# board_supply_440v.net
KiCad netlist of a schematic drawn in Altium Designer
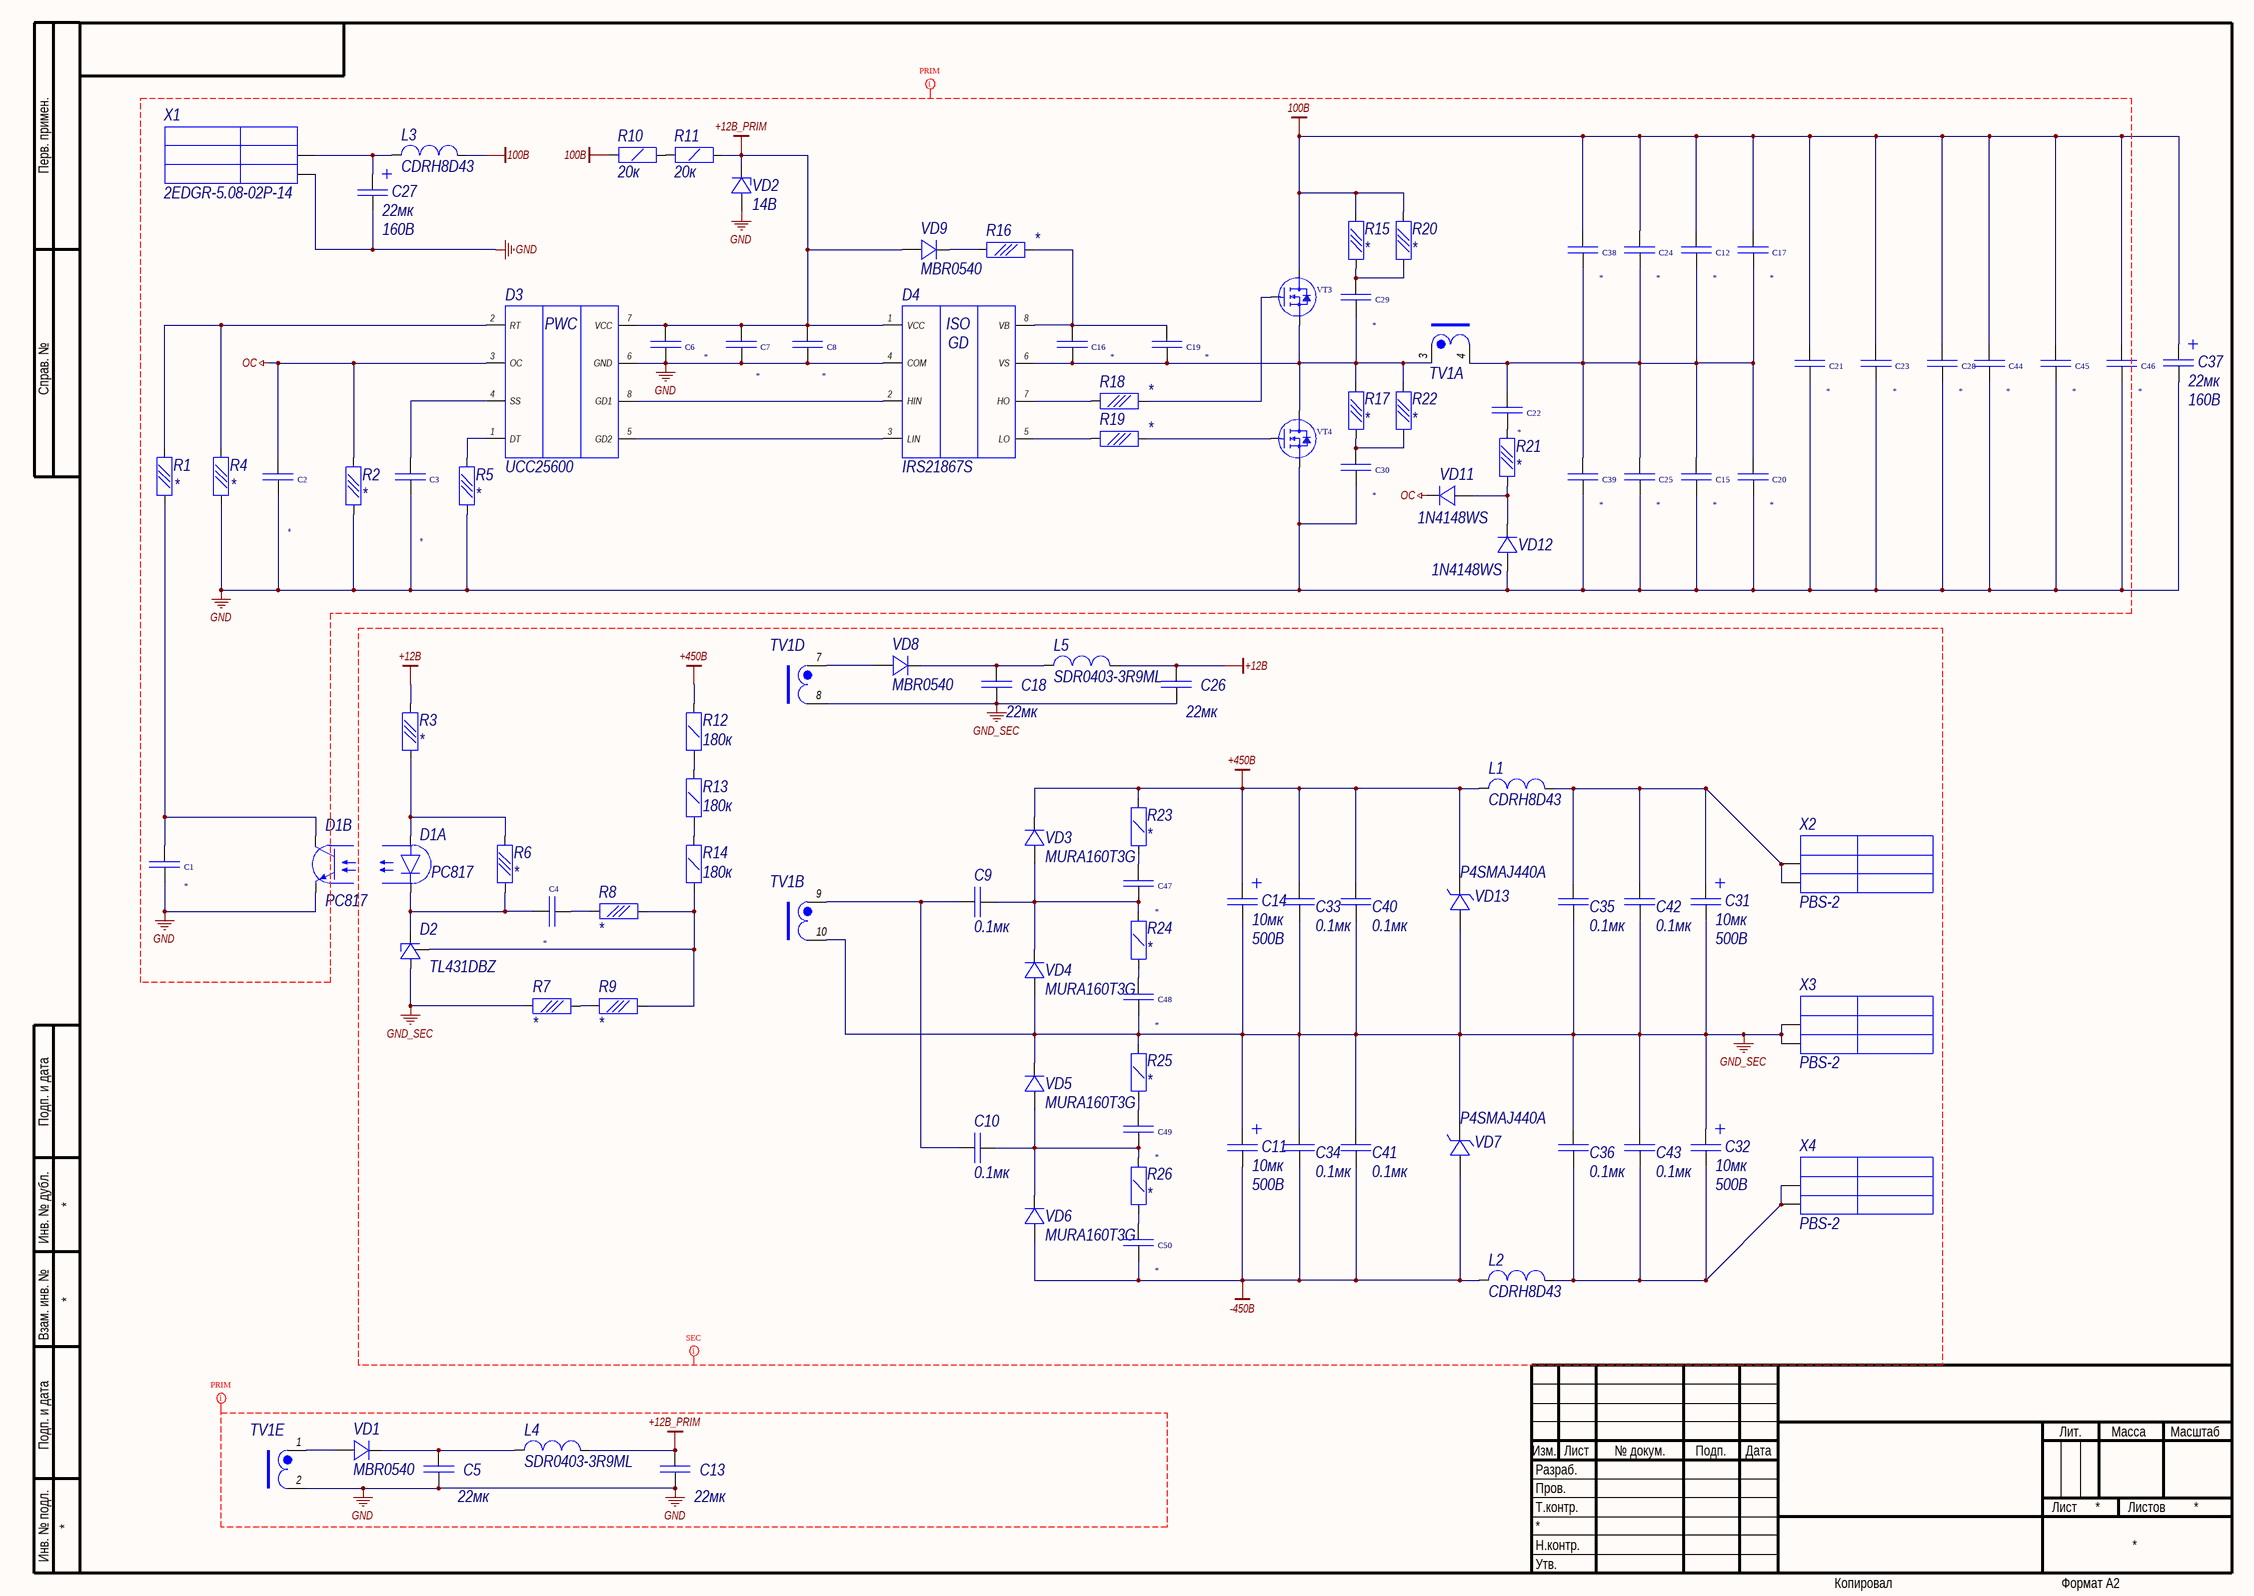
[diagram p0: board_supply_440v.SchDoc]

(export (version "E")
  (design (tool "Eeschema 10.0.6"))
  (components
    (comp (ref "C1") (value "*") (footprint "C-0603") (libsource (lib "Capacitor") (part "C0603")))
    (comp (ref "C2") (value "*") (footprint "C-0603") (libsource (lib "Capacitor") (part "C0603")))
    (comp (ref "C3") (value "*") (footprint "C-0603") (libsource (lib "Capacitor") (part "C0603")))
    (comp (ref "C4") (value "*") (footprint "C-0603") (libsource (lib "Capacitor") (part "C0603")))
    (comp (ref "C5")
      (value "22мк")
      (footprint "C-1206")
      (fields (field (name "VOLTAGE") "25"))
      (libsource (lib "Capacitor") (part "C1206"))
    )
    (comp (ref "C6") (value "*") (footprint "C-0603") (libsource (lib "Capacitor") (part "C0603")))
    (comp (ref "C7") (value "*") (footprint "C-0603") (libsource (lib "Capacitor") (part "C0603")))
    (comp (ref "C8") (value "*") (footprint "C-0603") (libsource (lib "Capacitor") (part "C0603")))
    (comp (ref "C9")
      (value "0.1мк")
      (footprint "C-1812")
      (fields (field (name "VOLTAGE") "630"))
      (libsource (lib "Capacitor") (part "C1812"))
    )
    (comp (ref "C10")
      (value "0.1мк")
      (footprint "C-1812")
      (fields (field (name "VOLTAGE") "630"))
      (libsource (lib "Capacitor") (part "C1812"))
    )
    (comp (ref "C11")
      (value "10мк")
      (footprint "CAP: D13C5H25")
      (description "Конденсатор электролитический")
      (fields (field (name "VOLTAGE") "500В"))
      (libsource (lib "Capacitor") (part "Aluminum electrolytic capacitor"))
    )
    (comp (ref "C12") (value "*") (footprint "C-0603") (libsource (lib "Capacitor") (part "C0603")))
    (comp (ref "C13")
      (value "22мк")
      (footprint "C-1206")
      (fields (field (name "VOLTAGE") "25"))
      (libsource (lib "Capacitor") (part "C1206"))
    )
    (comp (ref "C14")
      (value "10мк")
      (footprint "CAP: D13C5H25")
      (description "Конденсатор электролитический")
      (fields (field (name "VOLTAGE") "500В"))
      (libsource (lib "Capacitor") (part "Aluminum electrolytic capacitor"))
    )
    (comp (ref "C15") (value "*") (footprint "C-0603") (libsource (lib "Capacitor") (part "C0603")))
    (comp (ref "C16") (value "*") (footprint "C-0603") (libsource (lib "Capacitor") (part "C0603")))
    (comp (ref "C17") (value "*") (footprint "C-0603") (libsource (lib "Capacitor") (part "C0603")))
    (comp (ref "C18")
      (value "22мк")
      (footprint "C-1206")
      (fields (field (name "VOLTAGE") "25"))
      (libsource (lib "Capacitor") (part "C1206"))
    )
    (comp (ref "C19") (value "*") (footprint "C-0603") (libsource (lib "Capacitor") (part "C0603")))
    (comp (ref "C20") (value "*") (footprint "C-0603") (libsource (lib "Capacitor") (part "C0603")))
    (comp (ref "C21") (value "*") (footprint "C-0603") (libsource (lib "Capacitor") (part "C0603")))
    (comp (ref "C22") (value "*") (footprint "C-0603") (libsource (lib "Capacitor") (part "C0603")))
    (comp (ref "C23") (value "*") (footprint "C-0603") (libsource (lib "Capacitor") (part "C0603")))
    (comp (ref "C24") (value "*") (footprint "C-0603") (libsource (lib "Capacitor") (part "C0603")))
    (comp (ref "C25") (value "*") (footprint "C-0603") (libsource (lib "Capacitor") (part "C0603")))
    (comp (ref "C26")
      (value "22мк")
      (footprint "C-1206")
      (fields (field (name "VOLTAGE") "25"))
      (libsource (lib "Capacitor") (part "C1206"))
    )
    (comp (ref "C27")
      (value "22мк")
      (footprint "CAP: D10C5H16")
      (description "Конденсатор электролитический")
      (fields (field (name "VOLTAGE") "160В"))
      (libsource (lib "Capacitor") (part "Aluminum electrolytic capacitor"))
    )
    (comp (ref "C28") (value "*") (footprint "C-0603") (libsource (lib "Capacitor") (part "C0603")))
    (comp (ref "C29") (value "*") (footprint "C-0603") (libsource (lib "Capacitor") (part "C0603")))
    (comp (ref "C30") (value "*") (footprint "C-0603") (libsource (lib "Capacitor") (part "C0603")))
    (comp (ref "C31")
      (value "10мк")
      (footprint "CAP: D13C5H25")
      (description "Конденсатор электролитический")
      (fields (field (name "VOLTAGE") "500В"))
      (libsource (lib "Capacitor") (part "Aluminum electrolytic capacitor"))
    )
    (comp (ref "C32")
      (value "10мк")
      (footprint "CAP: D13C5H25")
      (description "Конденсатор электролитический")
      (fields (field (name "VOLTAGE") "500В"))
      (libsource (lib "Capacitor") (part "Aluminum electrolytic capacitor"))
    )
    (comp (ref "C33")
      (value "0.1мк")
      (footprint "C-1812")
      (fields (field (name "VOLTAGE") "630"))
      (libsource (lib "Capacitor") (part "C1812"))
    )
    (comp (ref "C34")
      (value "0.1мк")
      (footprint "C-1812")
      (fields (field (name "VOLTAGE") "630"))
      (libsource (lib "Capacitor") (part "C1812"))
    )
    (comp (ref "C35")
      (value "0.1мк")
      (footprint "C-1812")
      (fields (field (name "VOLTAGE") "630"))
      (libsource (lib "Capacitor") (part "C1812"))
    )
    (comp (ref "C36")
      (value "0.1мк")
      (footprint "C-1812")
      (fields (field (name "VOLTAGE") "630"))
      (libsource (lib "Capacitor") (part "C1812"))
    )
    (comp (ref "C37")
      (value "22мк")
      (footprint "CAP: D10C5H16")
      (description "Конденсатор электролитический")
      (fields (field (name "VOLTAGE") "160В"))
      (libsource (lib "Capacitor") (part "Aluminum electrolytic capacitor"))
    )
    (comp (ref "C38") (value "*") (footprint "C-0603") (libsource (lib "Capacitor") (part "C0603")))
    (comp (ref "C39") (value "*") (footprint "C-0603") (libsource (lib "Capacitor") (part "C0603")))
    (comp (ref "C40")
      (value "0.1мк")
      (footprint "C-1812")
      (fields (field (name "VOLTAGE") "630"))
      (libsource (lib "Capacitor") (part "C1812"))
    )
    (comp (ref "C41")
      (value "0.1мк")
      (footprint "C-1812")
      (fields (field (name "VOLTAGE") "630"))
      (libsource (lib "Capacitor") (part "C1812"))
    )
    (comp (ref "C42")
      (value "0.1мк")
      (footprint "C-1812")
      (fields (field (name "VOLTAGE") "630"))
      (libsource (lib "Capacitor") (part "C1812"))
    )
    (comp (ref "C43")
      (value "0.1мк")
      (footprint "C-1812")
      (fields (field (name "VOLTAGE") "630"))
      (libsource (lib "Capacitor") (part "C1812"))
    )
    (comp (ref "C44") (value "*") (footprint "C-0603") (libsource (lib "Capacitor") (part "C0603")))
    (comp (ref "C45") (value "*") (footprint "C-0603") (libsource (lib "Capacitor") (part "C0603")))
    (comp (ref "C46") (value "*") (footprint "C-0603") (libsource (lib "Capacitor") (part "C0603")))
    (comp (ref "C47") (value "*") (footprint "C-1206") (libsource (lib "Capacitor") (part "C1206")))
    (comp (ref "C48") (value "*") (footprint "C-1206") (libsource (lib "Capacitor") (part "C1206")))
    (comp (ref "C49") (value "*") (footprint "C-1206") (libsource (lib "Capacitor") (part "C1206")))
    (comp (ref "C50") (value "*") (footprint "C-1206") (libsource (lib "Capacitor") (part "C1206")))
    (comp (ref "D1")
      (value "PC817")
      (footprint "DIP4-SMD")
      (description "Оптрон с транзисторным выходом")
      (libsource (lib "OPTO") (part "PC817"))
    )
    (comp (ref "D2")
      (value "TL431DBZ")
      (footprint "SOT-23-3")
      (description "Микросхема ИОН")
      (libsource (lib "IC_Linear_Regulator") (part "TL431DBZ"))
    )
    (comp (ref "D3")
      (value "UCC25600")
      (footprint "8-SOIC")
      (description "Микросхема контроллер LLC")
      (libsource (lib "Power Controllers") (part "UCC25600"))
    )
    (comp (ref "D4")
      (value "IRS21867S")
      (footprint "8-SOIC")
      (description "Микросхема полумостовой драйвер")
      (libsource (lib "Power Controllers") (part "IRS21867S"))
    )
    (comp (ref "L1")
      (value "CDRH8D43")
      (footprint "L-8.3x8.3x4.5")
      (description "SMD дроссель")
      (libsource (lib "INDUCTORS") (part "CDRH8D43"))
    )
    (comp (ref "L2")
      (value "CDRH8D43")
      (footprint "L-8.3x8.3x4.5")
      (description "SMD дроссель")
      (libsource (lib "INDUCTORS") (part "CDRH8D43"))
    )
    (comp (ref "L3")
      (value "CDRH8D43")
      (footprint "L-8.3x8.3x4.5")
      (description "SMD дроссель")
      (libsource (lib "INDUCTORS") (part "CDRH8D43"))
    )
    (comp (ref "L4")
      (value "SDR0403-3R9ML")
      (footprint "L-4.5x4x3.2")
      (libsource (lib "INDUCTORS") (part "SDR0403-3R9ML"))
    )
    (comp (ref "L5")
      (value "SDR0403-3R9ML")
      (footprint "L-4.5x4x3.2")
      (libsource (lib "INDUCTORS") (part "SDR0403-3R9ML"))
    )
    (comp (ref "R1")
      (value "*")
      (footprint "R-0603")
      (description "Резистор SMD")
      (fields (field (name "TOLERANCE") "5%"))
      (libsource (lib "Resistor") (part "R0603"))
    )
    (comp (ref "R2")
      (value "*")
      (footprint "R-0603")
      (description "Резистор SMD")
      (fields (field (name "TOLERANCE") "5%"))
      (libsource (lib "Resistor") (part "R0603"))
    )
    (comp (ref "R3")
      (value "*")
      (footprint "R-0603")
      (description "Резистор SMD")
      (fields (field (name "TOLERANCE") "5%"))
      (libsource (lib "Resistor") (part "R0603"))
    )
    (comp (ref "R4")
      (value "*")
      (footprint "R-0603")
      (description "Резистор SMD")
      (fields (field (name "TOLERANCE") "5%"))
      (libsource (lib "Resistor") (part "R0603"))
    )
    (comp (ref "R5")
      (value "*")
      (footprint "R-0603")
      (description "Резистор SMD")
      (fields (field (name "TOLERANCE") "5%"))
      (libsource (lib "Resistor") (part "R0603"))
    )
    (comp (ref "R6")
      (value "*")
      (footprint "R-0603")
      (description "Резистор SMD")
      (fields (field (name "TOLERANCE") "5%"))
      (libsource (lib "Resistor") (part "R0603"))
    )
    (comp (ref "R7")
      (value "*")
      (footprint "R-0603")
      (description "Резистор SMD")
      (fields (field (name "TOLERANCE") "5%"))
      (libsource (lib "Resistor") (part "R0603"))
    )
    (comp (ref "R8")
      (value "*")
      (footprint "R-0603")
      (description "Резистор SMD")
      (fields (field (name "TOLERANCE") "5%"))
      (libsource (lib "Resistor") (part "R0603"))
    )
    (comp (ref "R9")
      (value "*")
      (footprint "R-0603")
      (description "Резистор SMD")
      (fields (field (name "TOLERANCE") "5%"))
      (libsource (lib "Resistor") (part "R0603"))
    )
    (comp (ref "R10")
      (value "20к")
      (footprint "R-1206")
      (description "Резистор SMD")
      (fields (field (name "TOLERANCE") "5%"))
      (libsource (lib "Resistor") (part "R1206"))
    )
    (comp (ref "R11")
      (value "20к")
      (footprint "R-1206")
      (description "Резистор SMD")
      (fields (field (name "TOLERANCE") "5%"))
      (libsource (lib "Resistor") (part "R1206"))
    )
    (comp (ref "R12")
      (value "180к")
      (footprint "R-1206")
      (description "Резистор SMD")
      (fields (field (name "TOLERANCE") "5%"))
      (libsource (lib "Resistor") (part "R1206"))
    )
    (comp (ref "R13")
      (value "180к")
      (footprint "R-1206")
      (description "Резистор SMD")
      (fields (field (name "TOLERANCE") "5%"))
      (libsource (lib "Resistor") (part "R1206"))
    )
    (comp (ref "R14")
      (value "180к")
      (footprint "R-1206")
      (description "Резистор SMD")
      (fields (field (name "TOLERANCE") "5%"))
      (libsource (lib "Resistor") (part "R1206"))
    )
    (comp (ref "R15")
      (value "*")
      (footprint "R-0603")
      (description "Резистор SMD")
      (fields (field (name "TOLERANCE") "5%"))
      (libsource (lib "Resistor") (part "R0603"))
    )
    (comp (ref "R16")
      (value "*")
      (footprint "R-0603")
      (description "Резистор SMD")
      (fields (field (name "TOLERANCE") "5%"))
      (libsource (lib "Resistor") (part "R0603"))
    )
    (comp (ref "R17")
      (value "*")
      (footprint "R-0603")
      (description "Резистор SMD")
      (fields (field (name "TOLERANCE") "5%"))
      (libsource (lib "Resistor") (part "R0603"))
    )
    (comp (ref "R18")
      (value "*")
      (footprint "R-0603")
      (description "Резистор SMD")
      (fields (field (name "TOLERANCE") "5%"))
      (libsource (lib "Resistor") (part "R0603"))
    )
    (comp (ref "R19")
      (value "*")
      (footprint "R-0603")
      (description "Резистор SMD")
      (fields (field (name "TOLERANCE") "5%"))
      (libsource (lib "Resistor") (part "R0603"))
    )
    (comp (ref "R20")
      (value "*")
      (footprint "R-0603")
      (description "Резистор SMD")
      (fields (field (name "TOLERANCE") "5%"))
      (libsource (lib "Resistor") (part "R0603"))
    )
    (comp (ref "R21")
      (value "*")
      (footprint "R-0603")
      (description "Резистор SMD")
      (fields (field (name "TOLERANCE") "5%"))
      (libsource (lib "Resistor") (part "R0603"))
    )
    (comp (ref "R22")
      (value "*")
      (footprint "R-0603")
      (description "Резистор SMD")
      (fields (field (name "TOLERANCE") "5%"))
      (libsource (lib "Resistor") (part "R0603"))
    )
    (comp (ref "R23")
      (value "*")
      (footprint "R-1206")
      (description "Резистор SMD")
      (fields (field (name "TOLERANCE") "5%"))
      (libsource (lib "Resistor") (part "R1206"))
    )
    (comp (ref "R24")
      (value "*")
      (footprint "R-1206")
      (description "Резистор SMD")
      (fields (field (name "TOLERANCE") "5%"))
      (libsource (lib "Resistor") (part "R1206"))
    )
    (comp (ref "R25")
      (value "*")
      (footprint "R-1206")
      (description "Резистор SMD")
      (fields (field (name "TOLERANCE") "5%"))
      (libsource (lib "Resistor") (part "R1206"))
    )
    (comp (ref "R26")
      (value "*")
      (footprint "R-1206")
      (description "Резистор SMD")
      (fields (field (name "TOLERANCE") "5%"))
      (libsource (lib "Resistor") (part "R1206"))
    )
    (comp (ref "TV1")
      (value "2xT26.9/14.7/11.2")
      (footprint "Transformers:EE30")
      (description "Трансформатор для board_supply_440v")
      (libsource (lib "Transformers") (part "2xT26.9/14.7/11.2"))
    )
    (comp (ref "VD1")
      (value "MBR0540")
      (footprint "SOD-123FL")
      (description "Диод выпрямительный одиночный")
      (libsource (lib "DIODES") (part "MBR0540"))
    )
    (comp (ref "VD2")
      (value "14В")
      (footprint "SOD-323")
      (description "Диод Зенера (стабилитрон)")
      (libsource (lib "DIODES") (part "MM3Z"))
    )
    (comp (ref "VD3")
      (value "MURA160T3G")
      (footprint "DO-214AC")
      (description "Диод выпрямительный одиночный")
      (libsource (lib "DIODES") (part "MURA160T3G"))
    )
    (comp (ref "VD4")
      (value "MURA160T3G")
      (footprint "DO-214AC")
      (description "Диод выпрямительный одиночный")
      (libsource (lib "DIODES") (part "MURA160T3G"))
    )
    (comp (ref "VD5")
      (value "MURA160T3G")
      (footprint "DO-214AC")
      (description "Диод выпрямительный одиночный")
      (libsource (lib "DIODES") (part "MURA160T3G"))
    )
    (comp (ref "VD6")
      (value "MURA160T3G")
      (footprint "DO-214AC")
      (description "Диод выпрямительный одиночный")
      (libsource (lib "DIODES") (part "MURA160T3G"))
    )
    (comp (ref "VD7")
      (value "P4SMAJ440A")
      (footprint "DO-214AC")
      (description "Защитный диод униполярный")
      (libsource (lib "DIODES") (part "P4SMAJ-XX-A"))
    )
    (comp (ref "VD8")
      (value "MBR0540")
      (footprint "SOD-123FL")
      (description "Диод выпрямительный одиночный")
      (libsource (lib "DIODES") (part "MBR0540"))
    )
    (comp (ref "VD9")
      (value "MBR0540")
      (footprint "SOD-123FL")
      (description "Диод выпрямительный одиночный")
      (libsource (lib "DIODES") (part "MBR0540"))
    )
    (comp (ref "VD11")
      (value "1N4148WS")
      (footprint "SOD-323")
      (description "Диод выпрямительный одиночный")
      (libsource (lib "DIODES") (part "1N4148WS"))
    )
    (comp (ref "VD12")
      (value "1N4148WS")
      (footprint "SOD-323")
      (description "Диод выпрямительный одиночный")
      (libsource (lib "DIODES") (part "1N4148WS"))
    )
    (comp (ref "VD13")
      (value "P4SMAJ440A")
      (footprint "DO-214AC")
      (description "Защитный диод униполярный")
      (libsource (lib "DIODES") (part "P4SMAJ-XX-A"))
    )
    (comp (ref "VT3")
      (value "__GENERIC-N")
      (footprint "WDFN-8")
      (description "Транзистор МОП, одиночный, N-канальный")
      (libsource (lib "MOSFET_POWER") (part "__GENERIC-N"))
    )
    (comp (ref "VT4")
      (value "__GENERIC-N")
      (footprint "WDFN-8")
      (description "Транзистор МОП, одиночный, N-канальный")
      (libsource (lib "MOSFET_POWER") (part "__GENERIC-N"))
    )
    (comp (ref "X1")
      (value "2EDGR-5.08-02P-14")
      (footprint "2EDGR-5.08-02P-14-00AH")
      (description "Разъем разрывной")
      (libsource (lib "CONNECTORS") (part "2EDGR-5.08-02P-14-00AH"))
    )
    (comp (ref "X2")
      (value "PBS-2")
      (footprint "PBS-2")
      (description "Разъём штыревой")
      (libsource (lib "CONNECTORS") (part "PBS-2"))
    )
    (comp (ref "X3")
      (value "PBS-2")
      (footprint "PBS-2")
      (description "Разъём штыревой")
      (libsource (lib "CONNECTORS") (part "PBS-2"))
    )
    (comp (ref "X4")
      (value "PBS-2")
      (footprint "PBS-2")
      (description "Разъём штыревой")
      (libsource (lib "CONNECTORS") (part "PBS-2"))
    )
  )
  (nets
    (net (code "1") (name "+12В") (class "Default")
      (node (ref "C26") (pin "1") (pintype "passive"))
      (node (ref "L5") (pin "1") (pinfunction "1_1") (pintype "passive"))
      (node (ref "R3") (pin "2") (pintype "passive"))
    )
    (net (code "2") (name "+12В_PRIM") (class "Default")
      (node (ref "C13") (pin "1") (pintype "passive"))
      (node (ref "C6") (pin "2") (pintype "passive"))
      (node (ref "C7") (pin "2") (pintype "passive"))
      (node (ref "C8") (pin "2") (pintype "passive"))
      (node (ref "D3") (pin "7") (pinfunction "VCC_7") (pintype "passive"))
      (node (ref "D4") (pin "1") (pinfunction "VCC_1") (pintype "passive"))
      (node (ref "L4") (pin "1") (pinfunction "1_1") (pintype "passive"))
      (node (ref "R11") (pin "1") (pintype "passive"))
      (node (ref "VD2") (pin "K") (pinfunction "K_K") (pintype "passive"))
      (node (ref "VD9") (pin "A") (pinfunction "A_A") (pintype "passive"))
    )
    (net (code "3") (name "+450В") (class "Default")
      (node (ref "C14") (pin "1") (pintype "passive"))
      (node (ref "C33") (pin "1") (pintype "passive"))
      (node (ref "C40") (pin "1") (pintype "passive"))
      (node (ref "L1") (pin "2") (pinfunction "2_2") (pintype "passive"))
      (node (ref "R12") (pin "2") (pintype "passive"))
      (node (ref "R23") (pin "1") (pintype "passive"))
      (node (ref "VD13") (pin "K") (pinfunction "K_K") (pintype "passive"))
      (node (ref "VD3") (pin "K") (pinfunction "K_K") (pintype "passive"))
    )
    (net (code "4") (name "-450В") (class "Default")
      (node (ref "C11") (pin "2") (pintype "passive"))
      (node (ref "C34") (pin "2") (pintype "passive"))
      (node (ref "C41") (pin "2") (pintype "passive"))
      (node (ref "C50") (pin "1") (pintype "passive"))
      (node (ref "L2") (pin "2") (pinfunction "2_2") (pintype "passive"))
      (node (ref "VD6") (pin "A") (pinfunction "A_A") (pintype "passive"))
      (node (ref "VD7") (pin "A") (pinfunction "A_A") (pintype "passive"))
    )
    (net (code "5") (name "100В") (class "Default")
      (node (ref "C12") (pin "2") (pintype "passive"))
      (node (ref "C17") (pin "2") (pintype "passive"))
      (node (ref "C21") (pin "2") (pintype "passive"))
      (node (ref "C23") (pin "2") (pintype "passive"))
      (node (ref "C24") (pin "2") (pintype "passive"))
      (node (ref "C28") (pin "2") (pintype "passive"))
      (node (ref "C37") (pin "1") (pintype "passive"))
      (node (ref "C38") (pin "2") (pintype "passive"))
      (node (ref "C44") (pin "2") (pintype "passive"))
      (node (ref "C45") (pin "2") (pintype "passive"))
      (node (ref "C46") (pin "2") (pintype "passive"))
      (node (ref "L3") (pin "1") (pinfunction "1_1") (pintype "passive"))
      (node (ref "R10") (pin "2") (pintype "passive"))
      (node (ref "R15") (pin "1") (pintype "passive"))
      (node (ref "R20") (pin "1") (pintype "passive"))
      (node (ref "VT3") (pin "D") (pinfunction "D_D") (pintype "passive"))
    )
    (net (code "6") (name "GND") (class "Default")
      (node (ref "C1") (pin "1") (pintype "passive"))
      (node (ref "C13") (pin "2") (pintype "passive"))
      (node (ref "C15") (pin "1") (pintype "passive"))
      (node (ref "C2") (pin "1") (pintype "passive"))
      (node (ref "C20") (pin "1") (pintype "passive"))
      (node (ref "C21") (pin "1") (pintype "passive"))
      (node (ref "C23") (pin "1") (pintype "passive"))
      (node (ref "C25") (pin "1") (pintype "passive"))
      (node (ref "C27") (pin "2") (pintype "passive"))
      (node (ref "C28") (pin "1") (pintype "passive"))
      (node (ref "C3") (pin "1") (pintype "passive"))
      (node (ref "C30") (pin "1") (pintype "passive"))
      (node (ref "C37") (pin "2") (pintype "passive"))
      (node (ref "C39") (pin "1") (pintype "passive"))
      (node (ref "C44") (pin "1") (pintype "passive"))
      (node (ref "C45") (pin "1") (pintype "passive"))
      (node (ref "C46") (pin "1") (pintype "passive"))
      (node (ref "C5") (pin "2") (pintype "passive"))
      (node (ref "C6") (pin "1") (pintype "passive"))
      (node (ref "C7") (pin "1") (pintype "passive"))
      (node (ref "C8") (pin "1") (pintype "passive"))
      (node (ref "D1") (pin "3") (pinfunction "E_3") (pintype "passive"))
      (node (ref "D3") (pin "6") (pinfunction "GND_6") (pintype "passive"))
      (node (ref "D4") (pin "4") (pinfunction "COM_4") (pintype "passive"))
      (node (ref "R2") (pin "1") (pintype "passive"))
      (node (ref "R4") (pin "1") (pintype "passive"))
      (node (ref "R5") (pin "1") (pintype "passive"))
      (node (ref "TV1") (pin "2") (pinfunction "2_2") (pintype "passive"))
      (node (ref "VD12") (pin "A") (pinfunction "A_A") (pintype "passive"))
      (node (ref "VD2") (pin "A") (pinfunction "A_A") (pintype "passive"))
      (node (ref "VT4") (pin "S") (pinfunction "S_S") (pintype "passive"))
      (node (ref "X1") (pin "2") (pintype "passive"))
    )
    (net (code "7") (name "GND_SEC") (class "Default")
      (node (ref "C11") (pin "1") (pintype "passive"))
      (node (ref "C14") (pin "2") (pintype "passive"))
      (node (ref "C18") (pin "2") (pintype "passive"))
      (node (ref "C26") (pin "2") (pintype "passive"))
      (node (ref "C31") (pin "2") (pintype "passive"))
      (node (ref "C32") (pin "1") (pintype "passive"))
      (node (ref "C33") (pin "2") (pintype "passive"))
      (node (ref "C34") (pin "1") (pintype "passive"))
      (node (ref "C35") (pin "2") (pintype "passive"))
      (node (ref "C36") (pin "1") (pintype "passive"))
      (node (ref "C40") (pin "2") (pintype "passive"))
      (node (ref "C41") (pin "1") (pintype "passive"))
      (node (ref "C42") (pin "2") (pintype "passive"))
      (node (ref "C43") (pin "1") (pintype "passive"))
      (node (ref "C48") (pin "1") (pintype "passive"))
      (node (ref "D2") (pin "3") (pinfunction "A_3") (pintype "passive"))
      (node (ref "R25") (pin "1") (pintype "passive"))
      (node (ref "R7") (pin "1") (pintype "passive"))
      (node (ref "TV1") (pin "10") (pinfunction "10_10") (pintype "passive"))
      (node (ref "TV1") (pin "8") (pinfunction "8_8") (pintype "passive"))
      (node (ref "VD13") (pin "A") (pinfunction "A_A") (pintype "passive"))
      (node (ref "VD4") (pin "A") (pinfunction "A_A") (pintype "passive"))
      (node (ref "VD5") (pin "K") (pinfunction "K_K") (pintype "passive"))
      (node (ref "VD7") (pin "K") (pinfunction "K_K") (pintype "passive"))
      (node (ref "X3") (pin "1") (pintype "passive"))
      (node (ref "X3") (pin "2") (pintype "passive"))
    )
    (net (code "8") (name "Net-(C4-Pad1)") (class "Default")
      (node (ref "C4") (pin "1") (pintype "passive"))
      (node (ref "R8") (pin "2") (pintype "passive"))
    )
    (net (code "9") (name "Net-(C5-Pad1)") (class "Default")
      (node (ref "C5") (pin "1") (pintype "passive"))
      (node (ref "L4") (pin "2") (pinfunction "2_2") (pintype "passive"))
      (node (ref "VD1") (pin "K") (pinfunction "K_K") (pintype "passive"))
    )
    (net (code "10") (name "Net-(C10-Pad1)") (class "Default")
      (node (ref "C10") (pin "1") (pintype "passive"))
      (node (ref "C49") (pin "1") (pintype "passive"))
      (node (ref "R26") (pin "1") (pintype "passive"))
      (node (ref "VD5") (pin "A") (pinfunction "A_A") (pintype "passive"))
      (node (ref "VD6") (pin "K") (pinfunction "K_K") (pintype "passive"))
    )
    (net (code "11") (name "Net-(C10-Pad2)") (class "Default")
      (node (ref "C10") (pin "2") (pintype "passive"))
      (node (ref "C9") (pin "2") (pintype "passive"))
      (node (ref "TV1") (pin "9") (pinfunction "9_9") (pintype "passive"))
    )
    (net (code "12") (name "Net-(C12-Pad1)") (class "Default")
      (node (ref "C12") (pin "1") (pintype "passive"))
      (node (ref "C15") (pin "2") (pintype "passive"))
      (node (ref "C17") (pin "1") (pintype "passive"))
      (node (ref "C20") (pin "2") (pintype "passive"))
      (node (ref "C22") (pin "1") (pintype "passive"))
      (node (ref "C24") (pin "1") (pintype "passive"))
      (node (ref "C25") (pin "2") (pintype "passive"))
      (node (ref "C38") (pin "1") (pintype "passive"))
      (node (ref "C39") (pin "2") (pintype "passive"))
      (node (ref "TV1") (pin "4") (pinfunction "4_4") (pintype "passive"))
    )
    (net (code "13") (name "Net-(C18-Pad1)") (class "Default")
      (node (ref "C18") (pin "1") (pintype "passive"))
      (node (ref "L5") (pin "2") (pinfunction "2_2") (pintype "passive"))
      (node (ref "VD8") (pin "K") (pinfunction "K_K") (pintype "passive"))
    )
    (net (code "14") (name "Net-(C22-Pad2)") (class "Default")
      (node (ref "C22") (pin "2") (pintype "passive"))
      (node (ref "R21") (pin "2") (pintype "passive"))
    )
    (net (code "15") (name "Net-(C27-Pad1)") (class "Default")
      (node (ref "C27") (pin "1") (pintype "passive"))
      (node (ref "L3") (pin "2") (pinfunction "2_2") (pintype "passive"))
      (node (ref "X1") (pin "1") (pintype "passive"))
    )
    (net (code "16") (name "Net-(C29-Pad2)") (class "Default")
      (node (ref "C29") (pin "2") (pintype "passive"))
      (node (ref "R15") (pin "2") (pintype "passive"))
      (node (ref "R20") (pin "2") (pintype "passive"))
    )
    (net (code "17") (name "Net-(C30-Pad2)") (class "Default")
      (node (ref "C30") (pin "2") (pintype "passive"))
      (node (ref "R17") (pin "2") (pintype "passive"))
      (node (ref "R22") (pin "2") (pintype "passive"))
    )
    (net (code "18") (name "Net-(C31-Pad1)") (class "Default")
      (node (ref "C31") (pin "1") (pintype "passive"))
      (node (ref "C35") (pin "1") (pintype "passive"))
      (node (ref "C42") (pin "1") (pintype "passive"))
      (node (ref "L1") (pin "1") (pinfunction "1_1") (pintype "passive"))
      (node (ref "X2") (pin "1") (pintype "passive"))
      (node (ref "X2") (pin "2") (pintype "passive"))
    )
    (net (code "19") (name "Net-(C32-Pad2)") (class "Default")
      (node (ref "C32") (pin "2") (pintype "passive"))
      (node (ref "C36") (pin "2") (pintype "passive"))
      (node (ref "C43") (pin "2") (pintype "passive"))
      (node (ref "L2") (pin "1") (pinfunction "1_1") (pintype "passive"))
      (node (ref "X4") (pin "1") (pintype "passive"))
      (node (ref "X4") (pin "2") (pintype "passive"))
    )
    (net (code "20") (name "Net-(C47-Pad1)") (class "Default")
      (node (ref "C47") (pin "1") (pintype "passive"))
      (node (ref "C9") (pin "1") (pintype "passive"))
      (node (ref "R24") (pin "1") (pintype "passive"))
      (node (ref "VD3") (pin "A") (pinfunction "A_A") (pintype "passive"))
      (node (ref "VD4") (pin "K") (pinfunction "K_K") (pintype "passive"))
    )
    (net (code "21") (name "Net-(C47-Pad2)") (class "Default")
      (node (ref "C47") (pin "2") (pintype "passive"))
      (node (ref "R23") (pin "2") (pintype "passive"))
    )
    (net (code "22") (name "Net-(C48-Pad2)") (class "Default")
      (node (ref "C48") (pin "2") (pintype "passive"))
      (node (ref "R24") (pin "2") (pintype "passive"))
    )
    (net (code "23") (name "Net-(C49-Pad2)") (class "Default")
      (node (ref "C49") (pin "2") (pintype "passive"))
      (node (ref "R25") (pin "2") (pintype "passive"))
    )
    (net (code "24") (name "Net-(C50-Pad2)") (class "Default")
      (node (ref "C50") (pin "2") (pintype "passive"))
      (node (ref "R26") (pin "2") (pintype "passive"))
    )
    (net (code "25") (name "Net-(D1A-A)") (class "Default")
      (node (ref "D1") (pin "1") (pinfunction "A_1") (pintype "passive"))
      (node (ref "R3") (pin "1") (pintype "passive"))
      (node (ref "R6") (pin "2") (pintype "passive"))
    )
    (net (code "26") (name "Net-(D1A-K)") (class "Default")
      (node (ref "C4") (pin "2") (pintype "passive"))
      (node (ref "D1") (pin "2") (pinfunction "K_2") (pintype "passive"))
      (node (ref "D2") (pin "1") (pinfunction "K_1") (pintype "passive"))
      (node (ref "R6") (pin "1") (pintype "passive"))
    )
    (net (code "27") (name "Net-(D1B-C)") (class "Default")
      (node (ref "C1") (pin "2") (pintype "passive"))
      (node (ref "D1") (pin "4") (pinfunction "C_4") (pintype "passive"))
      (node (ref "R1") (pin "1") (pintype "passive"))
    )
    (net (code "28") (name "Net-(D2-R)") (class "Default")
      (node (ref "D2") (pin "2") (pinfunction "R_2") (pintype "passive"))
      (node (ref "R14") (pin "1") (pintype "passive"))
      (node (ref "R8") (pin "1") (pintype "passive"))
      (node (ref "R9") (pin "2") (pintype "passive"))
    )
    (net (code "29") (name "Net-(D3-DT)") (class "Default")
      (node (ref "D3") (pin "1") (pinfunction "DT_1") (pintype "passive"))
      (node (ref "R5") (pin "2") (pintype "passive"))
    )
    (net (code "30") (name "Net-(D3-GD1)") (class "Default")
      (node (ref "D3") (pin "8") (pinfunction "GD1_8") (pintype "passive"))
      (node (ref "D4") (pin "2") (pinfunction "HIN_2") (pintype "passive"))
    )
    (net (code "31") (name "Net-(D3-GD2)") (class "Default")
      (node (ref "D3") (pin "5") (pinfunction "GD2_5") (pintype "passive"))
      (node (ref "D4") (pin "3") (pinfunction "LIN_3") (pintype "passive"))
    )
    (net (code "32") (name "Net-(D3-RT)") (class "Default")
      (node (ref "D3") (pin "2") (pinfunction "RT_2") (pintype "passive"))
      (node (ref "R1") (pin "2") (pintype "passive"))
      (node (ref "R4") (pin "2") (pintype "passive"))
    )
    (net (code "33") (name "Net-(D3-SS)") (class "Default")
      (node (ref "C3") (pin "2") (pintype "passive"))
      (node (ref "D3") (pin "4") (pinfunction "SS_4") (pintype "passive"))
    )
    (net (code "34") (name "Net-(D4-HO)") (class "Default")
      (node (ref "D4") (pin "7") (pinfunction "HO_7") (pintype "passive"))
      (node (ref "R18") (pin "1") (pintype "passive"))
    )
    (net (code "35") (name "Net-(D4-LO)") (class "Default")
      (node (ref "D4") (pin "5") (pinfunction "LO_5") (pintype "passive"))
      (node (ref "R19") (pin "1") (pintype "passive"))
    )
    (net (code "36") (name "Net-(D4-VB)") (class "Default")
      (node (ref "C16") (pin "2") (pintype "passive"))
      (node (ref "C19") (pin "2") (pintype "passive"))
      (node (ref "D4") (pin "8") (pinfunction "VB_8") (pintype "passive"))
      (node (ref "R16") (pin "2") (pintype "passive"))
    )
    (net (code "37") (name "Net-(D4-VS)") (class "Default")
      (node (ref "C16") (pin "1") (pintype "passive"))
      (node (ref "C19") (pin "1") (pintype "passive"))
      (node (ref "C29") (pin "1") (pintype "passive"))
      (node (ref "D4") (pin "6") (pinfunction "VS_6") (pintype "passive"))
      (node (ref "R17") (pin "1") (pintype "passive"))
      (node (ref "R22") (pin "1") (pintype "passive"))
      (node (ref "TV1") (pin "3") (pinfunction "3_3") (pintype "passive"))
      (node (ref "VT3") (pin "S") (pinfunction "S_S") (pintype "passive"))
      (node (ref "VT4") (pin "D") (pinfunction "D_D") (pintype "passive"))
    )
    (net (code "38") (name "Net-(R7-Pad2)") (class "Default")
      (node (ref "R7") (pin "2") (pintype "passive"))
      (node (ref "R9") (pin "1") (pintype "passive"))
    )
    (net (code "39") (name "Net-(R10-Pad1)") (class "Default")
      (node (ref "R10") (pin "1") (pintype "passive"))
      (node (ref "R11") (pin "2") (pintype "passive"))
    )
    (net (code "40") (name "Net-(R12-Pad1)") (class "Default")
      (node (ref "R12") (pin "1") (pintype "passive"))
      (node (ref "R13") (pin "2") (pintype "passive"))
    )
    (net (code "41") (name "Net-(R13-Pad1)") (class "Default")
      (node (ref "R13") (pin "1") (pintype "passive"))
      (node (ref "R14") (pin "2") (pintype "passive"))
    )
    (net (code "42") (name "Net-(R16-Pad1)") (class "Default")
      (node (ref "R16") (pin "1") (pintype "passive"))
      (node (ref "VD9") (pin "K") (pinfunction "K_K") (pintype "passive"))
    )
    (net (code "43") (name "Net-(R18-Pad2)") (class "Default")
      (node (ref "R18") (pin "2") (pintype "passive"))
      (node (ref "VT3") (pin "G") (pinfunction "G_G") (pintype "passive"))
    )
    (net (code "44") (name "Net-(R19-Pad2)") (class "Default")
      (node (ref "R19") (pin "2") (pintype "passive"))
      (node (ref "VT4") (pin "G") (pinfunction "G_G") (pintype "passive"))
    )
    (net (code "45") (name "Net-(R21-Pad1)") (class "Default")
      (node (ref "R21") (pin "1") (pintype "passive"))
      (node (ref "VD11") (pin "A") (pinfunction "A_A") (pintype "passive"))
      (node (ref "VD12") (pin "K") (pinfunction "K_K") (pintype "passive"))
    )
    (net (code "46") (name "Net-(TV1-Pad1)") (class "Default")
      (node (ref "TV1") (pin "1") (pinfunction "1_1") (pintype "passive"))
      (node (ref "VD1") (pin "A") (pinfunction "A_A") (pintype "passive"))
    )
    (net (code "47") (name "Net-(TV1-Pad7)") (class "Default")
      (node (ref "TV1") (pin "7") (pinfunction "7_7") (pintype "passive"))
      (node (ref "VD8") (pin "A") (pinfunction "A_A") (pintype "passive"))
    )
    (net (code "48") (name "OC") (class "Default")
      (node (ref "C2") (pin "2") (pintype "passive"))
      (node (ref "D3") (pin "3") (pinfunction "OC_3") (pintype "passive"))
      (node (ref "R2") (pin "2") (pintype "passive"))
      (node (ref "VD11") (pin "K") (pinfunction "K_K") (pintype "passive"))
    )
  )
)
